# Intdiff.net
KiCad netlist of a schematic drawn in Altium Designer
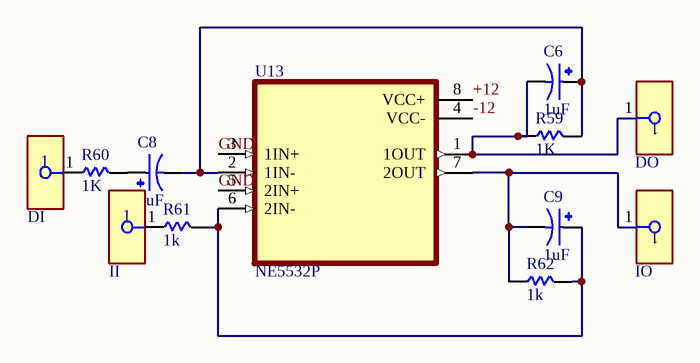
[diagram p0: Intdiff.SchDoc]

(export (version "E")
  (design (tool "Eeschema 10.0.6"))
  (components
    (comp (ref "C6")
      (value "1uF")
      (footprint "CAPPRD250W50D630H1250")
      (description "CAP ALUM 680UF 20% 63V THRU HOLE")
      (fields (field (name "MP") "EEU-FS1J681S") (field (name "MF") "Panasonic Electronic Components"))
      (libsource (lib "Schlib1") (part "EEUFS1J681S"))
    )
    (comp (ref "C8")
      (value "1uF")
      (footprint "CAPPRD250W50D630H1250")
      (description "CAP ALUM 680UF 20% 63V THRU HOLE")
      (fields (field (name "MP") "EEU-FS1J681S") (field (name "MF") "Panasonic Electronic Components"))
      (libsource (lib "") (part "EEUFS1J681S_1"))
    )
    (comp (ref "C9")
      (value "1uF")
      (footprint "CAPPRD250W50D630H1250")
      (description "CAP ALUM 680UF 20% 63V THRU HOLE")
      (fields (field (name "MP") "EEU-FS1J681S") (field (name "MF") "Panasonic Electronic Components"))
      (libsource (lib "Schlib1") (part "EEUFS1J681S"))
    )
    (comp (ref "DI")
      (value "1581-5")
      (footprint "FP-1581-5-MFG")
      (description "CONN BANANA JACK TURRET GREEN")
      (libsource (lib "") (part "CMP-73906-000011-1_1"))
    )
    (comp (ref "DO")
      (value "1581-5")
      (footprint "FP-1581-5-MFG")
      (description "CONN BANANA JACK TURRET GREEN")
      (libsource (lib "Schlib1") (part "CMP-73906-000011-1"))
    )
    (comp (ref "II")
      (value "1581-5")
      (footprint "FP-1581-5-MFG")
      (description "CONN BANANA JACK TURRET GREEN")
      (libsource (lib "") (part "CMP-73906-000011-1_1"))
    )
    (comp (ref "IO")
      (value "1581-5")
      (footprint "FP-1581-5-MFG")
      (description "CONN BANANA JACK TURRET GREEN")
      (libsource (lib "Schlib1") (part "CMP-73906-000011-1"))
    )
    (comp (ref "R59")
      (value "1K")
      (footprint "RESAD1100W55L680D260")
      (description "1.07 kOhms Â±1% 0.25W, 1/4W Through Hole Resistor Axial - Metal Film")
      (fields (field (name "MF") "Yageo") (field (name "MP") "MFR-25FBF52-1K"))
      (libsource (lib "Schlib1") (part "MFR-25FBF52-1K"))
    )
    (comp (ref "R60")
      (value "1K")
      (footprint "RESAD1100W55L680D260")
      (description "1.07 kOhms Â±1% 0.25W, 1/4W Through Hole Resistor Axial - Metal Film")
      (fields (field (name "MF") "Yageo") (field (name "MP") "MFR-25FBF52-1K"))
      (libsource (lib "Schlib1") (part "MFR-25FBF52-1K"))
    )
    (comp (ref "R61")
      (value "1k")
      (footprint "RESAD1100W55L680D260")
      (description "1.07 kOhms Â±1% 0.25W, 1/4W Through Hole Resistor Axial - Metal Film")
      (fields (field (name "MF") "Yageo") (field (name "MP") "MFR-25FBF52-1K"))
      (libsource (lib "Schlib1") (part "MFR-25FBF52-1K"))
    )
    (comp (ref "R62")
      (value "1k")
      (footprint "RESAD1100W55L680D260")
      (description "1.07 kOhms Â±1% 0.25W, 1/4W Through Hole Resistor Axial - Metal Film")
      (fields (field (name "MF") "Yageo") (field (name "MP") "MFR-25FBF52-1K"))
      (libsource (lib "Schlib1") (part "MFR-25FBF52-1K"))
    )
    (comp (ref "U13")
      (value "NE5532P")
      (footprint "DIP794W45P254L959H508Q8")
      (description "Dual, 30-V, 10-MHz, low-noise operational amplifier for audio applications")
      (fields (field (name "MF") "Texas Instruments"))
      (libsource (lib "Schlib1") (part "NE5532P"))
    )
  )
  (nets
    (net (code "1") (name "/+12") (class "Default")
      (node (ref "U13") (pin "8") (pinfunction "VCC+_8") (pintype "power_in"))
    )
    (net (code "2") (name "/-12") (class "Default")
      (node (ref "U13") (pin "4") (pinfunction "VCC-_4") (pintype "power_in"))
    )
    (net (code "3") (name "/GND") (class "Default")
      (node (ref "U13") (pin "3") (pinfunction "1IN+_3") (pintype "input"))
      (node (ref "U13") (pin "5") (pinfunction "2IN+_5") (pintype "input"))
    )
    (net (code "4") (name "Net-(C8-PadP)") (class "Default")
      (node (ref "C8") (pin "P") (pinfunction "P_P") (pintype "passive"))
      (node (ref "R60") (pin "2") (pinfunction "2_2") (pintype "passive"))
    )
    (net (code "5") (name "Net-(DI-Pad1)") (class "Default")
      (node (ref "DI") (pin "1") (pinfunction "1_1") (pintype "passive"))
      (node (ref "R60") (pin "1") (pinfunction "1_1") (pintype "passive"))
    )
    (net (code "6") (name "Net-(II-Pad1)") (class "Default")
      (node (ref "II") (pin "1") (pinfunction "1_1") (pintype "passive"))
      (node (ref "R61") (pin "1") (pinfunction "1_1") (pintype "passive"))
    )
    (net (code "7") (name "Net-(U13-1IN-)") (class "Default")
      (node (ref "C6") (pin "P") (pinfunction "P_P") (pintype "passive"))
      (node (ref "C8") (pin "N") (pinfunction "N_N") (pintype "passive"))
      (node (ref "R59") (pin "2") (pinfunction "2_2") (pintype "passive"))
      (node (ref "U13") (pin "2") (pinfunction "1IN-_2") (pintype "input"))
    )
    (net (code "8") (name "Net-(U13-1OUT)") (class "Default")
      (node (ref "C6") (pin "N") (pinfunction "N_N") (pintype "passive"))
      (node (ref "DO") (pin "1") (pinfunction "1_1") (pintype "passive"))
      (node (ref "R59") (pin "1") (pinfunction "1_1") (pintype "passive"))
      (node (ref "U13") (pin "1") (pinfunction "1OUT_1") (pintype "output"))
    )
    (net (code "9") (name "Net-(U13-2IN-)") (class "Default")
      (node (ref "C9") (pin "P") (pinfunction "P_P") (pintype "passive"))
      (node (ref "R61") (pin "2") (pinfunction "2_2") (pintype "passive"))
      (node (ref "R62") (pin "2") (pinfunction "2_2") (pintype "passive"))
      (node (ref "U13") (pin "6") (pinfunction "2IN-_6") (pintype "input"))
    )
    (net (code "10") (name "Net-(U13-2OUT)") (class "Default")
      (node (ref "C9") (pin "N") (pinfunction "N_N") (pintype "passive"))
      (node (ref "IO") (pin "1") (pinfunction "1_1") (pintype "passive"))
      (node (ref "R62") (pin "1") (pinfunction "1_1") (pintype "passive"))
      (node (ref "U13") (pin "7") (pinfunction "2OUT_7") (pintype "output"))
    )
  )
)
